# AVR.net
KiCad netlist of a schematic drawn in Altium Designer
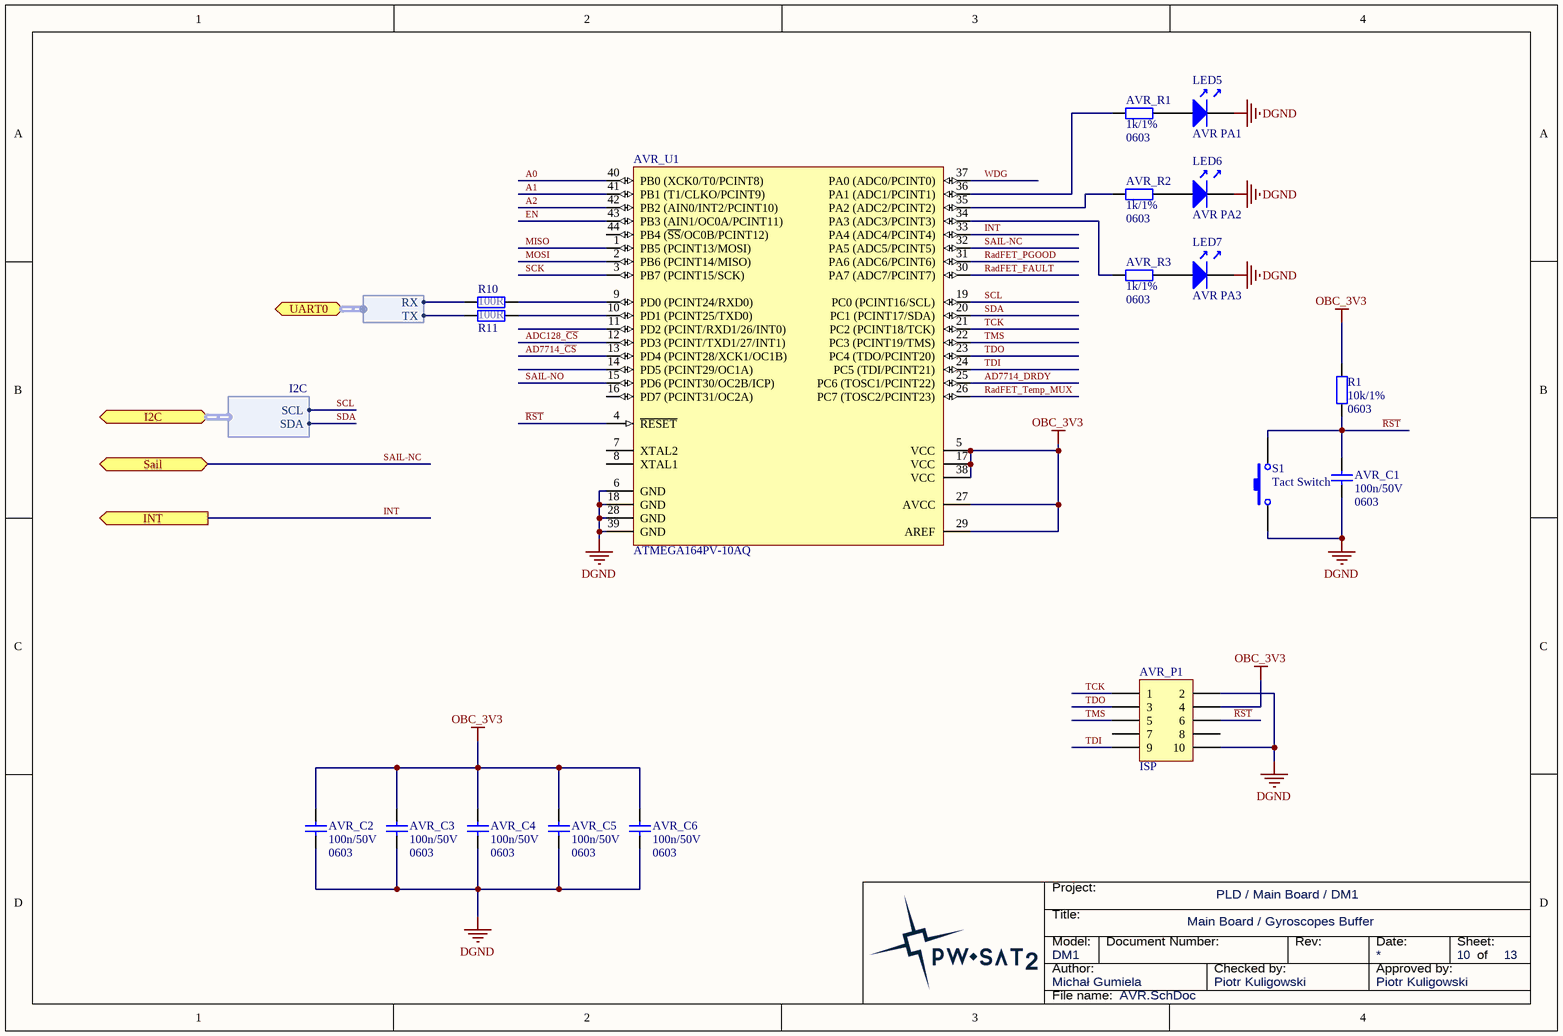
[diagram p0: AVR.SchDoc]

(export (version "E")
  (design (tool "Eeschema 10.0.6"))
  (components
    (comp (ref "AVR_C1")
      (value "100n/50V")
      (footprint "SMD_Capacitor_0603")
      (description "Ceramic Cap Kemet COTS 100n/50V X7R 0603")
      (fields
        (field (name "MANUFACTURER") "Kemet")
        (field (name "MANUFACTURERPARTNUMBER") "C0603T104K5RALTU")
        (field (name "PACKAGE") "0603")
      )
      (libsource (lib "capacitors") (part "Cer_C0603T104K5RALTU"))
    )
    (comp (ref "AVR_C2")
      (value "100n/50V")
      (footprint "SMD_Capacitor_0603")
      (description "Ceramic Cap Kemet COTS 100n/50V X7R 0603")
      (fields
        (field (name "MANUFACTURER") "Kemet")
        (field (name "MANUFACTURERPARTNUMBER") "C0603T104K5RALTU")
        (field (name "PACKAGE") "0603")
      )
      (libsource (lib "capacitors") (part "Cer_C0603T104K5RALTU"))
    )
    (comp (ref "AVR_C3")
      (value "100n/50V")
      (footprint "SMD_Capacitor_0603")
      (description "Ceramic Cap Kemet COTS 100n/50V X7R 0603")
      (fields
        (field (name "MANUFACTURER") "Kemet")
        (field (name "MANUFACTURERPARTNUMBER") "C0603T104K5RALTU")
        (field (name "PACKAGE") "0603")
      )
      (libsource (lib "capacitors") (part "Cer_C0603T104K5RALTU"))
    )
    (comp (ref "AVR_C4")
      (value "100n/50V")
      (footprint "SMD_Capacitor_0603")
      (description "Ceramic Cap Kemet COTS 100n/50V X7R 0603")
      (fields
        (field (name "MANUFACTURER") "Kemet")
        (field (name "MANUFACTURERPARTNUMBER") "C0603T104K5RALTU")
        (field (name "PACKAGE") "0603")
      )
      (libsource (lib "capacitors") (part "Cer_C0603T104K5RALTU"))
    )
    (comp (ref "AVR_C5")
      (value "100n/50V")
      (footprint "SMD_Capacitor_0603")
      (description "Ceramic Cap Kemet COTS 100n/50V X7R 0603")
      (fields
        (field (name "MANUFACTURER") "Kemet")
        (field (name "MANUFACTURERPARTNUMBER") "C0603T104K5RALTU")
        (field (name "PACKAGE") "0603")
      )
      (libsource (lib "capacitors") (part "Cer_C0603T104K5RALTU"))
    )
    (comp (ref "AVR_C6")
      (value "100n/50V")
      (footprint "SMD_Capacitor_0603")
      (description "Ceramic Cap Kemet COTS 100n/50V X7R 0603")
      (fields
        (field (name "MANUFACTURER") "Kemet")
        (field (name "MANUFACTURERPARTNUMBER") "C0603T104K5RALTU")
        (field (name "PACKAGE") "0603")
      )
      (libsource (lib "capacitors") (part "Cer_C0603T104K5RALTU"))
    )
    (comp (ref "AVR_P1")
      (value "ISP")
      (footprint "IDC-10-Male-Socket")
      (description "Header, 5-Pin, Dual row")
      (libsource (lib "GG") (part "Header 5X2"))
    )
    (comp (ref "AVR_R1")
      (value "1k/1%")
      (footprint "SMD_Resistor_0603")
      (description "1k/1% Vishay CRCW 0603 Resistor. 100mW, 100ppm, 75V.")
      (fields
        (field (name "MANUFACTURER") "Vishay")
        (field (name "MANUFACTURERPARTNUMBER") "CRCW06031K00FKxxxx")
        (field (name "PACKAGE") "0603")
      )
      (libsource (lib "resistors") (part "CRCW06031K00FKxxxx"))
    )
    (comp (ref "AVR_R2")
      (value "1k/1%")
      (footprint "SMD_Resistor_0603")
      (description "1k/1% Vishay CRCW 0603 Resistor. 100mW, 100ppm, 75V.")
      (fields
        (field (name "MANUFACTURER") "Vishay")
        (field (name "MANUFACTURERPARTNUMBER") "CRCW06031K00FKxxxx")
        (field (name "PACKAGE") "0603")
      )
      (libsource (lib "resistors") (part "CRCW06031K00FKxxxx"))
    )
    (comp (ref "AVR_R3")
      (value "1k/1%")
      (footprint "SMD_Resistor_0603")
      (description "1k/1% Vishay CRCW 0603 Resistor. 100mW, 100ppm, 75V.")
      (fields
        (field (name "MANUFACTURER") "Vishay")
        (field (name "MANUFACTURERPARTNUMBER") "CRCW06031K00FKxxxx")
        (field (name "PACKAGE") "0603")
      )
      (libsource (lib "resistors") (part "CRCW06031K00FKxxxx"))
    )
    (comp (ref "AVR_U1")
      (value "ATMEGA164PV-10AQ")
      (footprint "TQFP-44")
      (description "General-purpose microcontroller")
      (libsource (lib "microcircuits") (part "ATMEGA164PV-10AQ"))
    )
    (comp (ref "LED5")
      (value "AVR PA1")
      (footprint "SMD_LED_1206")
      (description "LED diode, SMD1206 package.")
      (libsource (lib "diodes") (part "LED-1206_RED"))
    )
    (comp (ref "LED6")
      (value "AVR PA2")
      (footprint "SMD_LED_1206")
      (description "LED diode, SMD1206 package.")
      (libsource (lib "diodes") (part "LED-1206_RED"))
    )
    (comp (ref "LED7")
      (value "AVR PA3")
      (footprint "SMD_LED_1206")
      (description "LED diode, SMD1206 package.")
      (libsource (lib "diodes") (part "LED-1206_RED"))
    )
    (comp (ref "R1")
      (value "10k/1%")
      (footprint "SMD_Resistor_0603")
      (description "10k/1% Vishay CRCW 0603 Resistor. 100mW, 100ppm, 75V.")
      (fields
        (field (name "MANUFACTURER") "Vishay")
        (field (name "MANUFACTURERPARTNUMBER") "CRCW060310K0FKxxxx")
        (field (name "PACKAGE") "0603")
      )
      (libsource (lib "resistors") (part "CRCW060310K0FKxxxx"))
    )
    (comp (ref "R10")
      (value "100R")
      (footprint "SMD_Resistor_0603")
      (description "10k/1% Vishay CRCW 0603 Resistor. 100mW, 100ppm, 75V.")
      (fields
        (field (name "MANUFACTURER") "Vishay")
        (field (name "MANUFACTURERPARTNUMBER") "CRCW060310K0FKxxxx")
      )
      (libsource (lib "") (part "CRCW060310K0FKxxxx_1"))
    )
    (comp (ref "R11")
      (value "100R")
      (footprint "SMD_Resistor_0603")
      (description "10k/1% Vishay CRCW 0603 Resistor. 100mW, 100ppm, 75V.")
      (fields
        (field (name "MANUFACTURER") "Vishay")
        (field (name "MANUFACTURERPARTNUMBER") "CRCW060310K0FKxxxx")
      )
      (libsource (lib "") (part "CRCW060310K0FKxxxx_2"))
    )
    (comp (ref "S1")
      (value "Tact Switch")
      (footprint "Tact Switch 3x6")
      (libsource (lib "switches") (part "TactSwitch"))
    )
  )
  (nets
    (net (code "3") (name "/A0") (class "Default")
      (node (ref "AVR_U1") (pin "40") (pinfunction "PB0_(XCK0/T0/PCINT8)_40") (pintype "bidirectional"))
    )
    (net (code "4") (name "/A1") (class "Default")
      (node (ref "AVR_U1") (pin "41") (pinfunction "PB1_(T1/CLKO/PCINT9)_41") (pintype "bidirectional"))
    )
    (net (code "5") (name "/A2") (class "Default")
      (node (ref "AVR_U1") (pin "42") (pinfunction "PB2_(AIN0/INT2/PCINT10)_42") (pintype "bidirectional"))
    )
    (net (code "6") (name "/AD7714_DRDY") (class "Default")
      (node (ref "AVR_U1") (pin "25") (pinfunction "PC6_(TOSC1/PCINT22)_25") (pintype "bidirectional"))
    )
    (net (code "7") (name "/AD7714_~{CS}") (class "Default")
      (node (ref "AVR_U1") (pin "13") (pinfunction "PD4_(PCINT28/XCK1/OC1B)_13") (pintype "bidirectional"))
    )
    (net (code "8") (name "/ADC128_~{CS}") (class "Default")
      (node (ref "AVR_U1") (pin "12") (pinfunction "PD3_(PCINT/TXD1/27/INT1)_12") (pintype "bidirectional"))
    )
    (net (code "9") (name "/EN") (class "Default")
      (node (ref "AVR_U1") (pin "43") (pinfunction "PB3_(AIN1/OC0A/PCINT11)_43") (pintype "bidirectional"))
    )
    (net (code "10") (name "/INT") (class "Default")
      (node (ref "AVR_U1") (pin "33") (pinfunction "PA4_(ADC4/PCINT4)_33") (pintype "bidirectional"))
    )
    (net (code "11") (name "/MISO") (class "Default")
      (node (ref "AVR_U1") (pin "1") (pinfunction "PB5_(PCINT13/MOSI)_1") (pintype "bidirectional"))
    )
    (net (code "12") (name "/MOSI") (class "Default")
      (node (ref "AVR_U1") (pin "2") (pinfunction "PB6_(PCINT14/MISO)_2") (pintype "bidirectional"))
    )
    (net (code "13") (name "/RX") (class "Default")
      (node (ref "R10") (pin "1") (pinfunction "1_1") (pintype "passive"))
    )
    (net (code "14") (name "/RadFET_FAULT") (class "Default")
      (node (ref "AVR_U1") (pin "30") (pinfunction "PA7_(ADC7/PCINT7)_30") (pintype "bidirectional"))
    )
    (net (code "15") (name "/RadFET_PGOOD") (class "Default")
      (node (ref "AVR_U1") (pin "31") (pinfunction "PA6_(ADC6/PCINT6)_31") (pintype "bidirectional"))
    )
    (net (code "16") (name "/RadFET_Temp_MUX") (class "Default")
      (node (ref "AVR_U1") (pin "26") (pinfunction "PC7_(TOSC2/PCINT23)_26") (pintype "bidirectional"))
    )
    (net (code "17") (name "/SAIL-NC") (class "Default")
      (node (ref "AVR_U1") (pin "32") (pinfunction "PA5_(ADC5/PCINT5)_32") (pintype "bidirectional"))
    )
    (net (code "18") (name "/SAIL-NO") (class "Default")
      (node (ref "AVR_U1") (pin "15") (pinfunction "PD6_(PCINT30/OC2B/ICP)_15") (pintype "bidirectional"))
    )
    (net (code "19") (name "/SCK") (class "Default")
      (node (ref "AVR_U1") (pin "3") (pinfunction "PB7_(PCINT15/SCK)_3") (pintype "bidirectional"))
    )
    (net (code "20") (name "/SCL") (class "Default")
      (node (ref "AVR_U1") (pin "19") (pinfunction "PC0_(PCINT16/SCL)_19") (pintype "bidirectional"))
    )
    (net (code "21") (name "/SDA") (class "Default")
      (node (ref "AVR_U1") (pin "20") (pinfunction "PC1_(PCINT17/SDA)_20") (pintype "bidirectional"))
    )
    (net (code "22") (name "/TCK") (class "Default")
      (node (ref "AVR_P1") (pin "1") (pinfunction "1_1") (pintype "passive"))
      (node (ref "AVR_U1") (pin "21") (pinfunction "PC2_(PCINT18/TCK)_21") (pintype "bidirectional"))
    )
    (net (code "23") (name "/TDI") (class "Default")
      (node (ref "AVR_P1") (pin "9") (pinfunction "9_9") (pintype "passive"))
      (node (ref "AVR_U1") (pin "24") (pinfunction "PC5_(TDI/PCINT21)_24") (pintype "bidirectional"))
    )
    (net (code "24") (name "/TDO") (class "Default")
      (node (ref "AVR_P1") (pin "3") (pinfunction "3_3") (pintype "passive"))
      (node (ref "AVR_U1") (pin "23") (pinfunction "PC4_(TDO/PCINT20)_23") (pintype "bidirectional"))
    )
    (net (code "25") (name "/TMS") (class "Default")
      (node (ref "AVR_P1") (pin "5") (pinfunction "5_5") (pintype "passive"))
      (node (ref "AVR_U1") (pin "22") (pinfunction "PC3_(PCINT19/TMS)_22") (pintype "bidirectional"))
    )
    (net (code "26") (name "/TX") (class "Default")
      (node (ref "R11") (pin "1") (pinfunction "1_1") (pintype "passive"))
    )
    (net (code "27") (name "/WDG") (class "Default")
      (node (ref "AVR_U1") (pin "37") (pinfunction "PA0_(ADC0/PCINT0)_37") (pintype "bidirectional"))
    )
    (net (code "30") (name "/~{RST}") (class "Default")
      (node (ref "AVR_C1") (pin "1") (pinfunction "1_1") (pintype "passive"))
      (node (ref "AVR_P1") (pin "6") (pinfunction "6_6") (pintype "passive"))
      (node (ref "AVR_U1") (pin "4") (pinfunction "~{RESET}_4") (pintype "input"))
      (node (ref "R1") (pin "2") (pinfunction "2_2") (pintype "passive"))
      (node (ref "S1") (pin "1") (pinfunction "1_1") (pintype "passive"))
    )
    (net (code "31") (name "DGND") (class "Default")
      (node (ref "AVR_C1") (pin "2") (pinfunction "2_2") (pintype "passive"))
      (node (ref "AVR_C2") (pin "2") (pinfunction "2_2") (pintype "passive"))
      (node (ref "AVR_C3") (pin "2") (pinfunction "2_2") (pintype "passive"))
      (node (ref "AVR_C4") (pin "2") (pinfunction "2_2") (pintype "passive"))
      (node (ref "AVR_C5") (pin "2") (pinfunction "2_2") (pintype "passive"))
      (node (ref "AVR_C6") (pin "2") (pinfunction "2_2") (pintype "passive"))
      (node (ref "AVR_P1") (pin "10") (pinfunction "10_10") (pintype "passive"))
      (node (ref "AVR_P1") (pin "2") (pinfunction "2_2") (pintype "passive"))
      (node (ref "AVR_U1") (pin "18") (pinfunction "GND_18") (pintype "power_in"))
      (node (ref "AVR_U1") (pin "28") (pinfunction "GND_28") (pintype "power_in"))
      (node (ref "AVR_U1") (pin "39") (pinfunction "GND_39") (pintype "power_in"))
      (node (ref "AVR_U1") (pin "6") (pinfunction "GND_6") (pintype "power_in"))
      (node (ref "LED5") (pin "K") (pinfunction "K_K") (pintype "passive"))
      (node (ref "LED6") (pin "K") (pinfunction "K_K") (pintype "passive"))
      (node (ref "LED7") (pin "K") (pinfunction "K_K") (pintype "passive"))
      (node (ref "S1") (pin "2") (pinfunction "2_2") (pintype "passive"))
    )
    (net (code "32") (name "Net-(AVR_R1-Pad2)") (class "Default")
      (node (ref "AVR_R1") (pin "2") (pinfunction "2_2") (pintype "passive"))
      (node (ref "LED5") (pin "A") (pinfunction "A_A") (pintype "passive"))
    )
    (net (code "33") (name "Net-(AVR_R2-Pad2)") (class "Default")
      (node (ref "AVR_R2") (pin "2") (pinfunction "2_2") (pintype "passive"))
      (node (ref "LED6") (pin "A") (pinfunction "A_A") (pintype "passive"))
    )
    (net (code "34") (name "Net-(AVR_R3-Pad2)") (class "Default")
      (node (ref "AVR_R3") (pin "2") (pinfunction "2_2") (pintype "passive"))
      (node (ref "LED7") (pin "A") (pinfunction "A_A") (pintype "passive"))
    )
    (net (code "35") (name "Net-(AVR_U1-PA1_(ADC1{slash}PCINT1))") (class "Default")
      (node (ref "AVR_R1") (pin "1") (pinfunction "1_1") (pintype "passive"))
      (node (ref "AVR_U1") (pin "36") (pinfunction "PA1_(ADC1/PCINT1)_36") (pintype "bidirectional"))
    )
    (net (code "36") (name "Net-(AVR_U1-PA2_(ADC2{slash}PCINT2))") (class "Default")
      (node (ref "AVR_R2") (pin "1") (pinfunction "1_1") (pintype "passive"))
      (node (ref "AVR_U1") (pin "35") (pinfunction "PA2_(ADC2/PCINT2)_35") (pintype "bidirectional"))
    )
    (net (code "37") (name "Net-(AVR_U1-PA3_(ADC3{slash}PCINT3))") (class "Default")
      (node (ref "AVR_R3") (pin "1") (pinfunction "1_1") (pintype "passive"))
      (node (ref "AVR_U1") (pin "34") (pinfunction "PA3_(ADC3/PCINT3)_34") (pintype "bidirectional"))
    )
    (net (code "38") (name "Net-(AVR_U1-PD0_(PCINT24{slash}RXD0))") (class "Default")
      (node (ref "AVR_U1") (pin "9") (pinfunction "PD0_(PCINT24/RXD0)_9") (pintype "bidirectional"))
      (node (ref "R10") (pin "2") (pinfunction "2_2") (pintype "passive"))
    )
    (net (code "39") (name "Net-(AVR_U1-PD1_(PCINT25{slash}TXD0))") (class "Default")
      (node (ref "AVR_U1") (pin "10") (pinfunction "PD1_(PCINT25/TXD0)_10") (pintype "bidirectional"))
      (node (ref "R11") (pin "2") (pinfunction "2_2") (pintype "passive"))
    )
    (net (code "40") (name "OBC_3V3") (class "Default")
      (node (ref "AVR_C2") (pin "1") (pinfunction "1_1") (pintype "passive"))
      (node (ref "AVR_C3") (pin "1") (pinfunction "1_1") (pintype "passive"))
      (node (ref "AVR_C4") (pin "1") (pinfunction "1_1") (pintype "passive"))
      (node (ref "AVR_C5") (pin "1") (pinfunction "1_1") (pintype "passive"))
      (node (ref "AVR_C6") (pin "1") (pinfunction "1_1") (pintype "passive"))
      (node (ref "AVR_P1") (pin "4") (pinfunction "4_4") (pintype "passive"))
      (node (ref "AVR_U1") (pin "17") (pinfunction "VCC_17") (pintype "power_in"))
      (node (ref "AVR_U1") (pin "27") (pinfunction "AVCC_27") (pintype "power_in"))
      (node (ref "AVR_U1") (pin "29") (pinfunction "AREF_29") (pintype "power_in"))
      (node (ref "AVR_U1") (pin "38") (pinfunction "VCC_38") (pintype "power_in"))
      (node (ref "AVR_U1") (pin "5") (pinfunction "VCC_5") (pintype "power_in"))
      (node (ref "R1") (pin "1") (pinfunction "1_1") (pintype "passive"))
    )
    (net (code "41") (name "unconnected-(AVR_P1-Pad7)") (class "Default")
      (node (ref "AVR_P1") (pin "7") (pinfunction "7_7") (pintype "passive"))
    )
    (net (code "42") (name "unconnected-(AVR_P1-Pad8)") (class "Default")
      (node (ref "AVR_P1") (pin "8") (pinfunction "8_8") (pintype "passive"))
    )
    (net (code "43") (name "unconnected-(AVR_U1-PB4_(~{SS}{slash}OC0B{slash}PCINT12)-Pad44)") (class "Default")
      (node (ref "AVR_U1") (pin "44") (pinfunction "PB4_(~{SS}/OC0B/PCINT12)_44") (pintype "bidirectional"))
    )
    (net (code "44") (name "unconnected-(AVR_U1-PD2_(PCINT{slash}RXD1{slash}26{slash}INT0)-Pad11)") (class "Default")
      (node (ref "AVR_U1") (pin "11") (pinfunction "PD2_(PCINT/RXD1/26/INT0)_11") (pintype "bidirectional"))
    )
    (net (code "45") (name "unconnected-(AVR_U1-PD5_(PCINT29{slash}OC1A)-Pad14)") (class "Default")
      (node (ref "AVR_U1") (pin "14") (pinfunction "PD5_(PCINT29/OC1A)_14") (pintype "bidirectional"))
    )
    (net (code "46") (name "unconnected-(AVR_U1-PD7_(PCINT31{slash}OC2A)-Pad16)") (class "Default")
      (node (ref "AVR_U1") (pin "16") (pinfunction "PD7_(PCINT31/OC2A)_16") (pintype "bidirectional"))
    )
    (net (code "47") (name "unconnected-(AVR_U1-XTAL1-Pad8)") (class "Default")
      (node (ref "AVR_U1") (pin "8") (pinfunction "XTAL1_8") (pintype "passive"))
    )
    (net (code "48") (name "unconnected-(AVR_U1-XTAL2-Pad7)") (class "Default")
      (node (ref "AVR_U1") (pin "7") (pinfunction "XTAL2_7") (pintype "passive"))
    )
  )
)
